# SCH_Robot_Arm_2022-05-23.net
KiCad netlist of a schematic drawn in EasyEDA
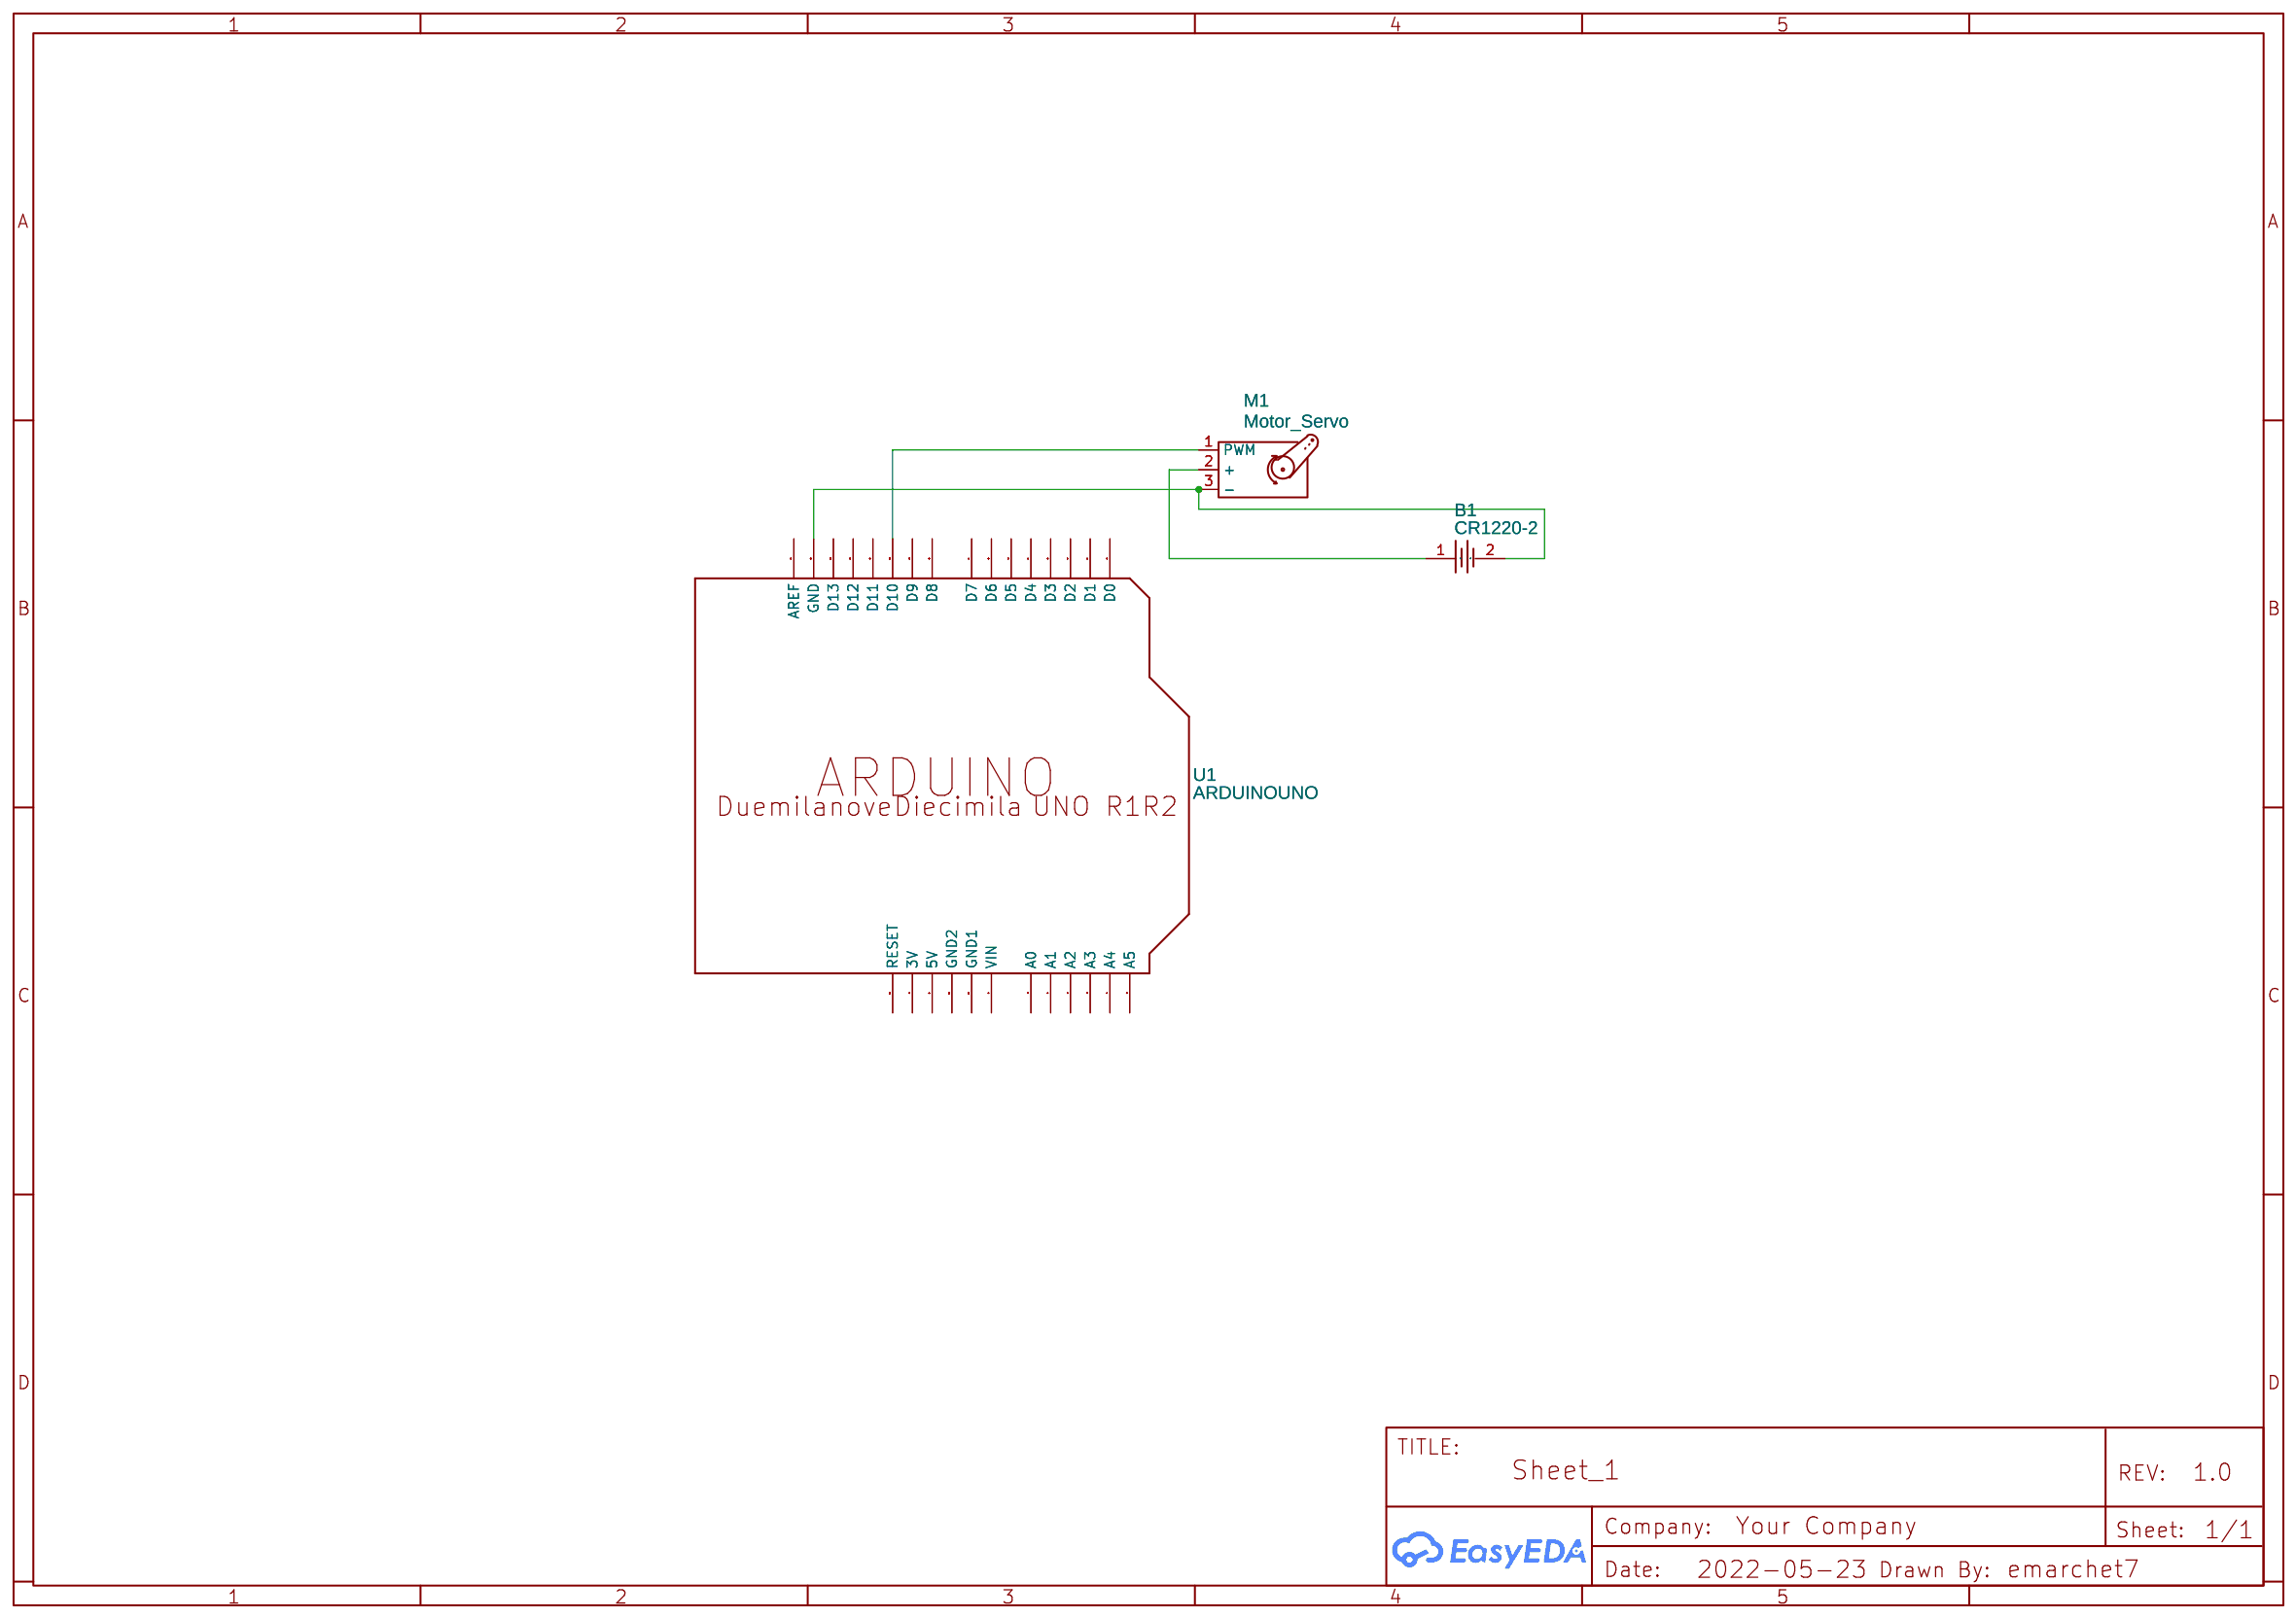
[diagram p0: schematic sheet]

(export (version "E")
  (design (tool "Eeschema 10.0.6"))
  (components
    (comp (ref "B1")
      (value "CR1220-2")
      (fields (field (name "BOM_Supplier Part") "C70381"))
      (libsource (lib "") (part "CR1220-2"))
    )
    (comp (ref "M1") (value "Motor_Servo") (libsource (lib "") (part "Motor_Servo")))
    (comp (ref "U1") (value "ARDUINOUNO") (libsource (lib "") (part "ARDUINOUNO")))
  )
  (nets
    (net (code "1") (name "Net-(M1-+)") (class "Default")
      (node (ref "B1") (pin "1") (pinfunction "1_1") (pintype "input"))
      (node (ref "M1") (pin "2") (pinfunction "+_2") (pintype "unspecified"))
    )
    (net (code "2") (name "Net-(M1--)") (class "Default")
      (node (ref "B1") (pin "2") (pinfunction "2_2") (pintype "input"))
      (node (ref "M1") (pin "3") (pinfunction "-_3") (pintype "unspecified"))
      (node (ref "U1") (pin "GND") (pinfunction "GND_GND") (pintype "passive"))
    )
    (net (code "3") (name "Net-(M1-PWM)") (class "Default")
      (node (ref "M1") (pin "1") (pinfunction "PWM_1") (pintype "unspecified"))
      (node (ref "U1") (pin "D10") (pinfunction "D10_D10") (pintype "unspecified"))
    )
    (net (code "4") (name "unconnected-(U1-Pad3V)") (class "Default")
      (node (ref "U1") (pin "3V") (pinfunction "3V_3V") (pintype "passive"))
    )
    (net (code "5") (name "unconnected-(U1-Pad5V)") (class "Default")
      (node (ref "U1") (pin "5V") (pinfunction "5V_5V") (pintype "passive"))
    )
    (net (code "6") (name "unconnected-(U1-PadA0)") (class "Default")
      (node (ref "U1") (pin "A0") (pinfunction "A0_A0") (pintype "unspecified"))
    )
    (net (code "7") (name "unconnected-(U1-PadA1)") (class "Default")
      (node (ref "U1") (pin "A1") (pinfunction "A1_A1") (pintype "unspecified"))
    )
    (net (code "8") (name "unconnected-(U1-PadA2)") (class "Default")
      (node (ref "U1") (pin "A2") (pinfunction "A2_A2") (pintype "unspecified"))
    )
    (net (code "9") (name "unconnected-(U1-PadA3)") (class "Default")
      (node (ref "U1") (pin "A3") (pinfunction "A3_A3") (pintype "unspecified"))
    )
    (net (code "10") (name "unconnected-(U1-PadA4)") (class "Default")
      (node (ref "U1") (pin "A4") (pinfunction "A4_A4") (pintype "unspecified"))
    )
    (net (code "11") (name "unconnected-(U1-PadA5)") (class "Default")
      (node (ref "U1") (pin "A5") (pinfunction "A5_A5") (pintype "unspecified"))
    )
    (net (code "12") (name "unconnected-(U1-PadAREF)") (class "Default")
      (node (ref "U1") (pin "AREF") (pinfunction "AREF_AREF") (pintype "unspecified"))
    )
    (net (code "13") (name "unconnected-(U1-PadD0)") (class "Default")
      (node (ref "U1") (pin "D0") (pinfunction "D0_D0") (pintype "unspecified"))
    )
    (net (code "14") (name "unconnected-(U1-PadD1)") (class "Default")
      (node (ref "U1") (pin "D1") (pinfunction "D1_D1") (pintype "unspecified"))
    )
    (net (code "15") (name "unconnected-(U1-PadD2)") (class "Default")
      (node (ref "U1") (pin "D2") (pinfunction "D2_D2") (pintype "unspecified"))
    )
    (net (code "16") (name "unconnected-(U1-PadD3)") (class "Default")
      (node (ref "U1") (pin "D3") (pinfunction "D3_D3") (pintype "unspecified"))
    )
    (net (code "17") (name "unconnected-(U1-PadD4)") (class "Default")
      (node (ref "U1") (pin "D4") (pinfunction "D4_D4") (pintype "unspecified"))
    )
    (net (code "18") (name "unconnected-(U1-PadD5)") (class "Default")
      (node (ref "U1") (pin "D5") (pinfunction "D5_D5") (pintype "unspecified"))
    )
    (net (code "19") (name "unconnected-(U1-PadD6)") (class "Default")
      (node (ref "U1") (pin "D6") (pinfunction "D6_D6") (pintype "unspecified"))
    )
    (net (code "20") (name "unconnected-(U1-PadD7)") (class "Default")
      (node (ref "U1") (pin "D7") (pinfunction "D7_D7") (pintype "unspecified"))
    )
    (net (code "21") (name "unconnected-(U1-PadD8)") (class "Default")
      (node (ref "U1") (pin "D8") (pinfunction "D8_D8") (pintype "unspecified"))
    )
    (net (code "22") (name "unconnected-(U1-PadD9)") (class "Default")
      (node (ref "U1") (pin "D9") (pinfunction "D9_D9") (pintype "unspecified"))
    )
    (net (code "23") (name "unconnected-(U1-PadD11)") (class "Default")
      (node (ref "U1") (pin "D11") (pinfunction "D11_D11") (pintype "unspecified"))
    )
    (net (code "24") (name "unconnected-(U1-PadD12)") (class "Default")
      (node (ref "U1") (pin "D12") (pinfunction "D12_D12") (pintype "unspecified"))
    )
    (net (code "25") (name "unconnected-(U1-PadD13)") (class "Default")
      (node (ref "U1") (pin "D13") (pinfunction "D13_D13") (pintype "unspecified"))
    )
    (net (code "26") (name "unconnected-(U1-PadGND1)") (class "Default")
      (node (ref "U1") (pin "GND1") (pinfunction "GND1_GND1") (pintype "passive"))
    )
    (net (code "27") (name "unconnected-(U1-PadGND2)") (class "Default")
      (node (ref "U1") (pin "GND2") (pinfunction "GND2_GND2") (pintype "passive"))
    )
    (net (code "28") (name "unconnected-(U1-PadRESET)") (class "Default")
      (node (ref "U1") (pin "RESET") (pinfunction "RESET_RESET") (pintype "unspecified"))
    )
    (net (code "29") (name "unconnected-(U1-PadVIN)") (class "Default")
      (node (ref "U1") (pin "VIN") (pinfunction "VIN_VIN") (pintype "passive"))
    )
  )
)
